# gpi-ctl.net
KiCad netlist of a schematic drawn in EAGLE
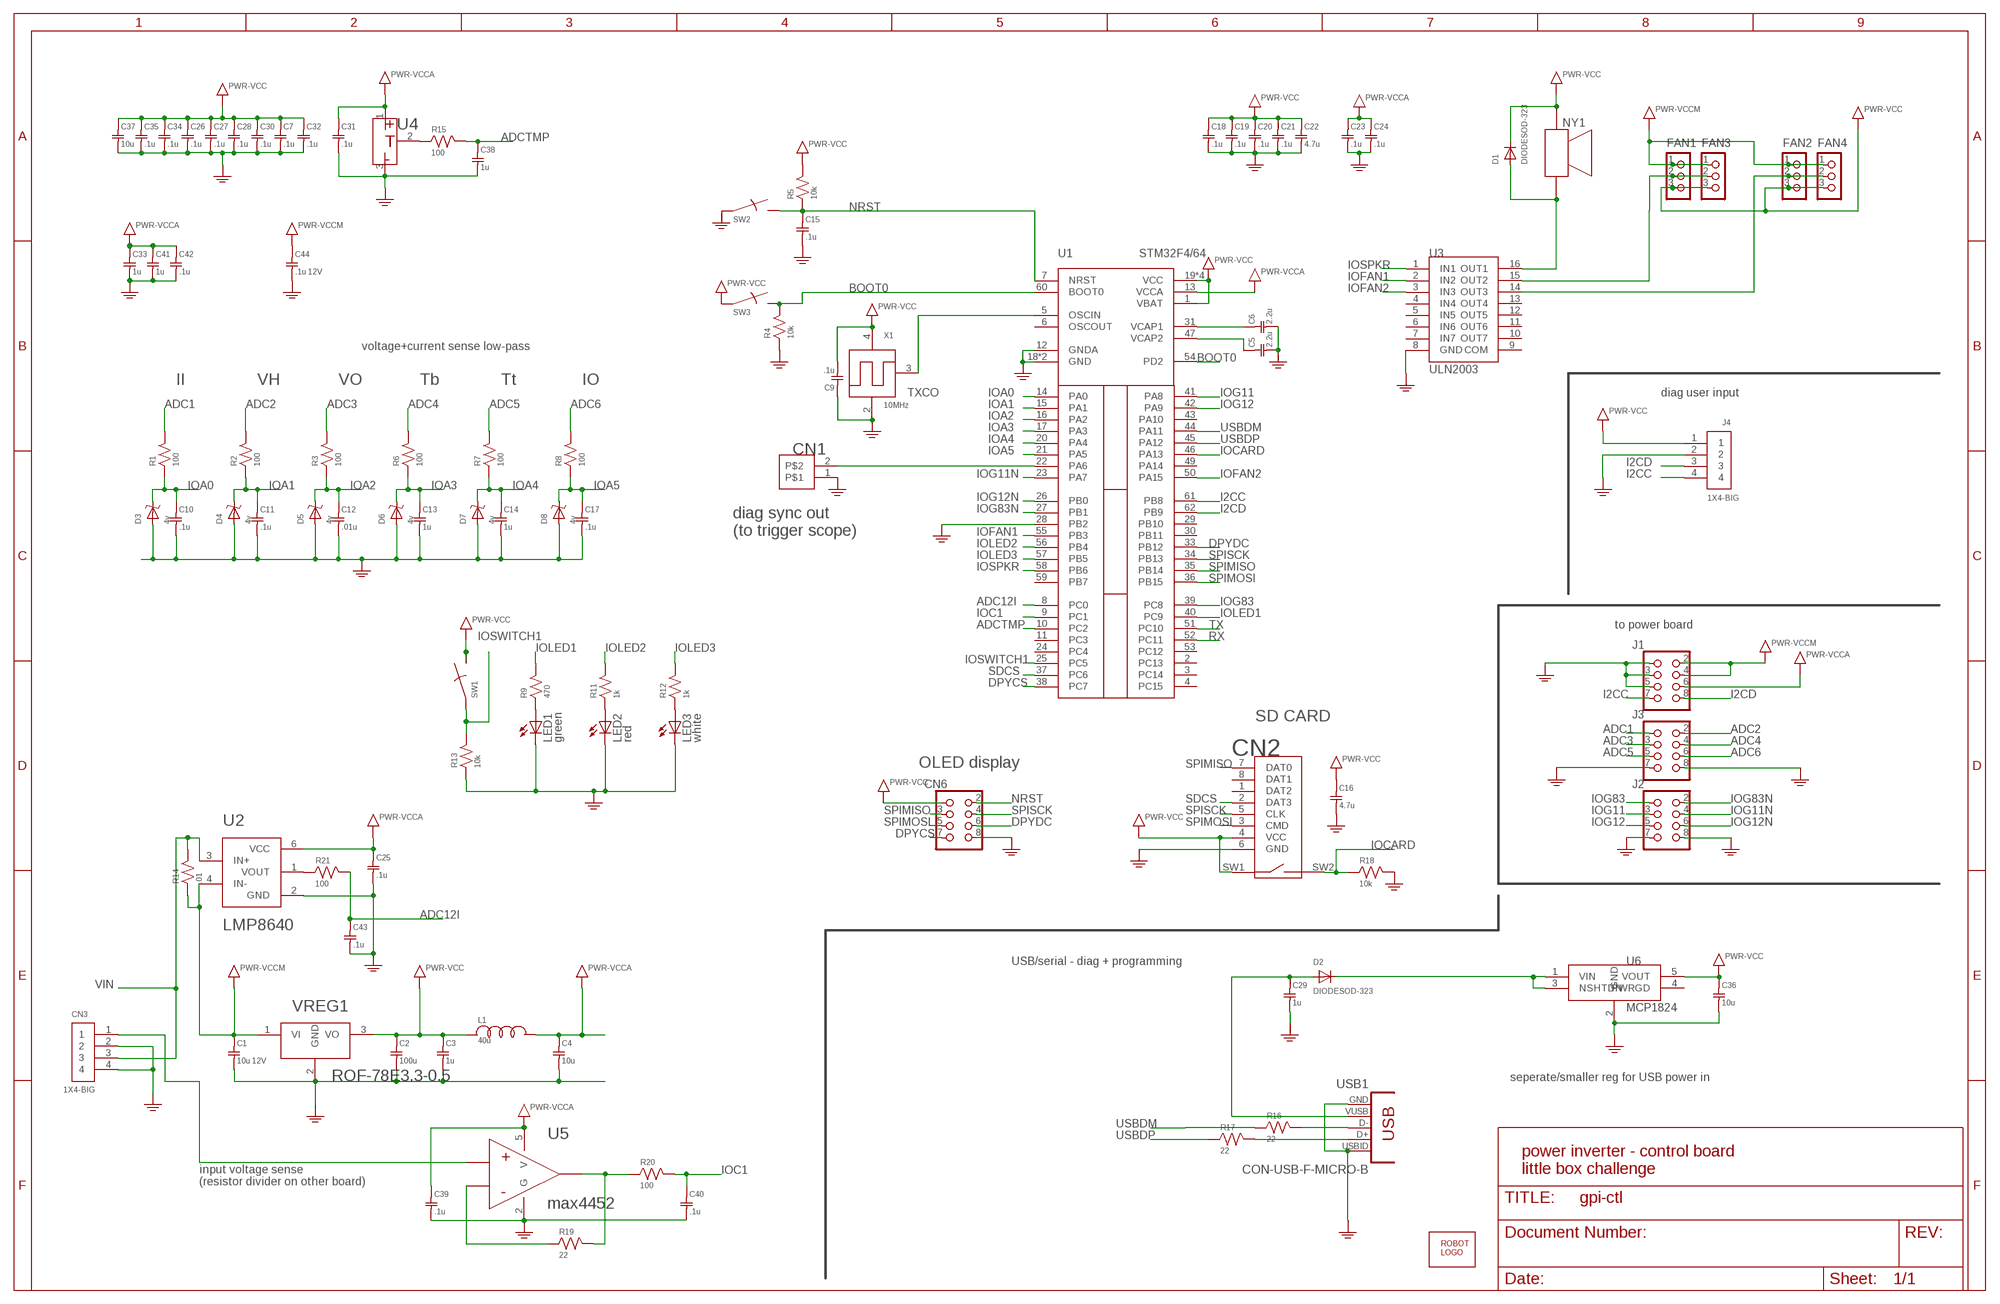
[diagram p0: schematic, sheet 1]

(export (version "E")
  (design (tool "Eeschema 10.0.6"))
  (components
    (comp (ref "C1")
      (value "10u 12V")
      (footprint "eagle-import:SMD0603")
      (libsource (lib "eagle-import") (part "C0603"))
    )
    (comp (ref "C2")
      (value "100u")
      (footprint "eagle-import:SMD1210")
      (libsource (lib "eagle-import") (part "C1210"))
    )
    (comp (ref "C3")
      (value "1u")
      (footprint "eagle-import:SMD0603")
      (libsource (lib "eagle-import") (part "C0603"))
    )
    (comp (ref "C4")
      (value "10u")
      (footprint "eagle-import:SMD0603")
      (libsource (lib "eagle-import") (part "C0603"))
    )
    (comp (ref "C5")
      (value "2.2u")
      (footprint "eagle-import:SMD0603")
      (libsource (lib "eagle-import") (part "C0603"))
    )
    (comp (ref "C6")
      (value "2.2u")
      (footprint "eagle-import:SMD0603")
      (libsource (lib "eagle-import") (part "C0603"))
    )
    (comp (ref "C7")
      (value ".1u")
      (footprint "eagle-import:SMD0603")
      (libsource (lib "eagle-import") (part "C0603"))
    )
    (comp (ref "C9")
      (value ".1u")
      (footprint "eagle-import:SMD0603")
      (libsource (lib "eagle-import") (part "C0603"))
    )
    (comp (ref "C10")
      (value ".1u")
      (footprint "eagle-import:SMD0603")
      (libsource (lib "eagle-import") (part "C0603"))
    )
    (comp (ref "C11")
      (value ".1u")
      (footprint "eagle-import:SMD0603")
      (libsource (lib "eagle-import") (part "C0603"))
    )
    (comp (ref "C12")
      (value ".01u")
      (footprint "eagle-import:SMD0603")
      (libsource (lib "eagle-import") (part "C0603"))
    )
    (comp (ref "C13")
      (value "1u")
      (footprint "eagle-import:SMD0603")
      (libsource (lib "eagle-import") (part "C0603"))
    )
    (comp (ref "C14")
      (value "1u")
      (footprint "eagle-import:SMD0603")
      (libsource (lib "eagle-import") (part "C0603"))
    )
    (comp (ref "C15")
      (value ".1u")
      (footprint "eagle-import:SMD0603")
      (libsource (lib "eagle-import") (part "C0603"))
    )
    (comp (ref "C16")
      (value "4.7u")
      (footprint "eagle-import:SMD0603")
      (libsource (lib "eagle-import") (part "C0603"))
    )
    (comp (ref "C17")
      (value ".1u")
      (footprint "eagle-import:SMD0603")
      (libsource (lib "eagle-import") (part "C0603"))
    )
    (comp (ref "C18")
      (value ".1u")
      (footprint "eagle-import:SMD0603")
      (libsource (lib "eagle-import") (part "C0603"))
    )
    (comp (ref "C19")
      (value ".1u")
      (footprint "eagle-import:SMD0603")
      (libsource (lib "eagle-import") (part "C0603"))
    )
    (comp (ref "C20")
      (value ".1u")
      (footprint "eagle-import:SMD0603")
      (libsource (lib "eagle-import") (part "C0603"))
    )
    (comp (ref "C21")
      (value ".1u")
      (footprint "eagle-import:SMD0603")
      (libsource (lib "eagle-import") (part "C0603"))
    )
    (comp (ref "C22")
      (value "4.7u")
      (footprint "eagle-import:SMD0603")
      (libsource (lib "eagle-import") (part "C0603"))
    )
    (comp (ref "C23")
      (value ".1u")
      (footprint "eagle-import:SMD0603")
      (libsource (lib "eagle-import") (part "C0603"))
    )
    (comp (ref "C24")
      (value ".1u")
      (footprint "eagle-import:SMD0603")
      (libsource (lib "eagle-import") (part "C0603"))
    )
    (comp (ref "C25")
      (value ".1u")
      (footprint "eagle-import:SMD0603")
      (libsource (lib "eagle-import") (part "C0603"))
    )
    (comp (ref "C26")
      (value ".1u")
      (footprint "eagle-import:SMD0603")
      (libsource (lib "eagle-import") (part "C0603"))
    )
    (comp (ref "C27")
      (value ".1u")
      (footprint "eagle-import:SMD0603")
      (libsource (lib "eagle-import") (part "C0603"))
    )
    (comp (ref "C28")
      (value ".1u")
      (footprint "eagle-import:SMD0603")
      (libsource (lib "eagle-import") (part "C0603"))
    )
    (comp (ref "C29")
      (value "1u")
      (footprint "eagle-import:SMD0603")
      (libsource (lib "eagle-import") (part "C0603"))
    )
    (comp (ref "C30")
      (value ".1u")
      (footprint "eagle-import:SMD0603")
      (libsource (lib "eagle-import") (part "C0603"))
    )
    (comp (ref "C31")
      (value ".1u")
      (footprint "eagle-import:SMD0603")
      (libsource (lib "eagle-import") (part "C0603"))
    )
    (comp (ref "C32")
      (value ".1u")
      (footprint "eagle-import:SMD0603")
      (libsource (lib "eagle-import") (part "C0603"))
    )
    (comp (ref "C33")
      (value "1u")
      (footprint "eagle-import:SMD0603")
      (libsource (lib "eagle-import") (part "C0603"))
    )
    (comp (ref "C34")
      (value ".1u")
      (footprint "eagle-import:SMD0603")
      (libsource (lib "eagle-import") (part "C0603"))
    )
    (comp (ref "C35")
      (value ".1u")
      (footprint "eagle-import:SMD0603")
      (libsource (lib "eagle-import") (part "C0603"))
    )
    (comp (ref "C36")
      (value "10u")
      (footprint "eagle-import:SMD0603")
      (libsource (lib "eagle-import") (part "C0603"))
    )
    (comp (ref "C37")
      (value "10u")
      (footprint "eagle-import:SMD0603")
      (libsource (lib "eagle-import") (part "C0603"))
    )
    (comp (ref "C38")
      (value "1u")
      (footprint "eagle-import:SMD0603")
      (libsource (lib "eagle-import") (part "C0603"))
    )
    (comp (ref "C39")
      (value ".1u")
      (footprint "eagle-import:SMD0603")
      (libsource (lib "eagle-import") (part "C0603"))
    )
    (comp (ref "C40")
      (value ".1u")
      (footprint "eagle-import:SMD0603")
      (libsource (lib "eagle-import") (part "C0603"))
    )
    (comp (ref "C41")
      (value "1u")
      (footprint "eagle-import:SMD0603")
      (libsource (lib "eagle-import") (part "C0603"))
    )
    (comp (ref "C42")
      (value ".1u")
      (footprint "eagle-import:SMD0603")
      (libsource (lib "eagle-import") (part "C0603"))
    )
    (comp (ref "C43")
      (value ".1u")
      (footprint "eagle-import:SMD0603")
      (libsource (lib "eagle-import") (part "C0603"))
    )
    (comp (ref "C44")
      (value ".1u 12V")
      (footprint "eagle-import:SMD0603")
      (libsource (lib "eagle-import") (part "C0603"))
    )
    (comp (ref "CN1")
      (value "HEADER-1X2.4")
      (footprint "eagle-import:HEADER-1X2-THM-WIDE")
      (libsource (lib "eagle-import") (part "HEADER-1X2.4"))
    )
    (comp (ref "CN2")
      (value "MICROSDPLAIN")
      (footprint "eagle-import:MICROSD_MOLEX_FRONT_PLAIN")
      (libsource (lib "eagle-import") (part "MICROSDPLAIN"))
    )
    (comp (ref "CN3")
      (value "1X4-BIG")
      (footprint "eagle-import:1X04-BIG")
      (libsource (lib "eagle-import") (part "1X4-BIG"))
    )
    (comp (ref "CN6")
      (value "HEADER-2X4")
      (footprint "eagle-import:HEADER-2X04")
      (libsource (lib "eagle-import") (part "HEADER-2X4"))
    )
    (comp (ref "D1")
      (value "DIODESOD-323")
      (footprint "eagle-import:SOD-323")
      (libsource (lib "eagle-import") (part "DIODESOD-323"))
    )
    (comp (ref "D2")
      (value "DIODESOD-323")
      (footprint "eagle-import:SOD-323")
      (libsource (lib "eagle-import") (part "DIODESOD-323"))
    )
    (comp (ref "D3")
      (value "4v")
      (footprint "eagle-import:SOD-323")
      (libsource (lib "eagle-import") (part "ZENER"))
    )
    (comp (ref "D4")
      (value "4v")
      (footprint "eagle-import:SOD-323")
      (libsource (lib "eagle-import") (part "ZENER"))
    )
    (comp (ref "D5")
      (value "4v")
      (footprint "eagle-import:SOD-323")
      (libsource (lib "eagle-import") (part "ZENER"))
    )
    (comp (ref "D6")
      (value "4v")
      (footprint "eagle-import:SOD-323")
      (libsource (lib "eagle-import") (part "ZENER"))
    )
    (comp (ref "D7")
      (value "4v")
      (footprint "eagle-import:SOD-323")
      (libsource (lib "eagle-import") (part "ZENER"))
    )
    (comp (ref "D8")
      (value "4v")
      (footprint "eagle-import:SOD-323")
      (libsource (lib "eagle-import") (part "ZENER"))
    )
    (comp (ref "FAN1")
      (value "CON_HEADER_1X03-PTH")
      (footprint "eagle-import:M1X3")
      (libsource (lib "eagle-import") (part "CON_HEADER_1X03-PTH"))
    )
    (comp (ref "FAN2")
      (value "CON_HEADER_1X03-PTH")
      (footprint "eagle-import:M1X3")
      (libsource (lib "eagle-import") (part "CON_HEADER_1X03-PTH"))
    )
    (comp (ref "FAN3")
      (value "CON_HEADER_1X03-PTH")
      (footprint "eagle-import:M1X3")
      (libsource (lib "eagle-import") (part "CON_HEADER_1X03-PTH"))
    )
    (comp (ref "FAN4")
      (value "CON_HEADER_1X03-PTH")
      (footprint "eagle-import:M1X3")
      (libsource (lib "eagle-import") (part "CON_HEADER_1X03-PTH"))
    )
    (comp (ref "J1")
      (value "HEADER-2X4")
      (footprint "eagle-import:HEADER-2X04")
      (libsource (lib "eagle-import") (part "HEADER-2X4"))
    )
    (comp (ref "J2")
      (value "HEADER-2X4")
      (footprint "eagle-import:HEADER-2X04")
      (libsource (lib "eagle-import") (part "HEADER-2X4"))
    )
    (comp (ref "J3")
      (value "HEADER-2X4")
      (footprint "eagle-import:HEADER-2X04")
      (libsource (lib "eagle-import") (part "HEADER-2X4"))
    )
    (comp (ref "J4")
      (value "1X4-BIG")
      (footprint "eagle-import:1X04-BIG")
      (libsource (lib "eagle-import") (part "1X4-BIG"))
    )
    (comp (ref "L1")
      (value "40u")
      (footprint "eagle-import:SMD0603")
      (libsource (lib "eagle-import") (part "LSMD0603"))
    )
    (comp (ref "LED1")
      (value "green")
      (footprint "eagle-import:LED3MM")
      (libsource (lib "eagle-import") (part "LED3MM"))
    )
    (comp (ref "LED2")
      (value "red")
      (footprint "eagle-import:LED3MM")
      (libsource (lib "eagle-import") (part "LED3MM"))
    )
    (comp (ref "LED3")
      (value "white")
      (footprint "eagle-import:LED3MM")
      (libsource (lib "eagle-import") (part "LED3MM"))
    )
    (comp (ref "NY1")
      (value "PUI-5040")
      (footprint "eagle-import:PUI-0540")
      (libsource (lib "eagle-import") (part "PUI-5040"))
    )
    (comp (ref "R1")
      (value "100")
      (footprint "eagle-import:SMD0603")
      (libsource (lib "eagle-import") (part "R0603"))
    )
    (comp (ref "R2")
      (value "100")
      (footprint "eagle-import:SMD0603")
      (libsource (lib "eagle-import") (part "R0603"))
    )
    (comp (ref "R3")
      (value "100")
      (footprint "eagle-import:SMD0603")
      (libsource (lib "eagle-import") (part "R0603"))
    )
    (comp (ref "R4")
      (value "10k")
      (footprint "eagle-import:SMD0603")
      (libsource (lib "eagle-import") (part "R0603"))
    )
    (comp (ref "R5")
      (value "10k")
      (footprint "eagle-import:SMD0603")
      (libsource (lib "eagle-import") (part "R0603"))
    )
    (comp (ref "R6")
      (value "100")
      (footprint "eagle-import:SMD0603")
      (libsource (lib "eagle-import") (part "R0603"))
    )
    (comp (ref "R7")
      (value "100")
      (footprint "eagle-import:SMD0603")
      (libsource (lib "eagle-import") (part "R0603"))
    )
    (comp (ref "R8")
      (value "100")
      (footprint "eagle-import:SMD0603")
      (libsource (lib "eagle-import") (part "R0603"))
    )
    (comp (ref "R9")
      (value "470")
      (footprint "eagle-import:SMD0603")
      (libsource (lib "eagle-import") (part "R0603"))
    )
    (comp (ref "R11")
      (value "1k")
      (footprint "eagle-import:SMD0603")
      (libsource (lib "eagle-import") (part "R0603"))
    )
    (comp (ref "R12")
      (value "1k")
      (footprint "eagle-import:SMD0603")
      (libsource (lib "eagle-import") (part "R0603"))
    )
    (comp (ref "R13")
      (value "10k")
      (footprint "eagle-import:SMD0603")
      (libsource (lib "eagle-import") (part "R0603"))
    )
    (comp (ref "R14")
      (value ".01")
      (footprint "eagle-import:SMD0805")
      (libsource (lib "eagle-import") (part "R0805"))
    )
    (comp (ref "R15")
      (value "100")
      (footprint "eagle-import:SMD0603")
      (libsource (lib "eagle-import") (part "R0603"))
    )
    (comp (ref "R16")
      (value "22")
      (footprint "eagle-import:SMD0603")
      (libsource (lib "eagle-import") (part "R0603"))
    )
    (comp (ref "R17")
      (value "22")
      (footprint "eagle-import:SMD0603")
      (libsource (lib "eagle-import") (part "R0603"))
    )
    (comp (ref "R18")
      (value "10k")
      (footprint "eagle-import:SMD0603")
      (libsource (lib "eagle-import") (part "R0603"))
    )
    (comp (ref "R19")
      (value "22")
      (footprint "eagle-import:SMD0603")
      (libsource (lib "eagle-import") (part "R0603"))
    )
    (comp (ref "R20")
      (value "100")
      (footprint "eagle-import:SMD0603")
      (libsource (lib "eagle-import") (part "R0603"))
    )
    (comp (ref "R21")
      (value "100")
      (footprint "eagle-import:SMD0603")
      (libsource (lib "eagle-import") (part "R0603"))
    )
    (comp (ref "SW1")
      (value "SWITCHGT12-THOLE")
      (footprint "eagle-import:SWITCH-GT12MCBE")
      (libsource (lib "eagle-import") (part "SWITCHGT12-THOLE"))
    )
    (comp (ref "SW2")
      (value "SWITCHKMR211")
      (footprint "eagle-import:KMR211")
      (libsource (lib "eagle-import") (part "SWITCHKMR211"))
    )
    (comp (ref "SW3")
      (value "SWITCHKMR211")
      (footprint "eagle-import:KMR211")
      (libsource (lib "eagle-import") (part "SWITCHKMR211"))
    )
    (comp (ref "U$1")
      (value "ROBOTMAN-LOGO")
      (footprint "eagle-import:ROBOTMAN-LOGO")
      (libsource (lib "eagle-import") (part "ROBOTMAN-LOGO"))
    )
    (comp (ref "U1")
      (value "STM32F4/64")
      (footprint "eagle-import:TQFP64")
      (libsource (lib "eagle-import") (part "STM32F4/64"))
    )
    (comp (ref "U2")
      (value "LMP8640")
      (footprint "eagle-import:SOT-6")
      (libsource (lib "eagle-import") (part "LMP8640"))
    )
    (comp (ref "U3")
      (value "ULN2003")
      (footprint "eagle-import:TSSOP-16")
      (libsource (lib "eagle-import") (part "ULN2003"))
    )
    (comp (ref "U4")
      (value "TEMPERATURE")
      (footprint "eagle-import:SOT-23")
      (libsource (lib "eagle-import") (part "TEMPERATURE"))
    )
    (comp (ref "U5")
      (value "max4452")
      (footprint "eagle-import:SOT-23-5")
      (libsource (lib "eagle-import") (part "OPAMP"))
    )
    (comp (ref "U6")
      (value "MCP1824")
      (footprint "eagle-import:SOT-23-5")
      (libsource (lib "eagle-import") (part "MCP1824"))
    )
    (comp (ref "USB1")
      (value "CON-USB-F-MICRO-B")
      (footprint "eagle-import:CONN_USB_MICRO-B")
      (libsource (lib "eagle-import") (part "CON-USB-F-MICRO-B"))
    )
    (comp (ref "VREG1")
      (value "ROF-78E3.3-0.5")
      (footprint "eagle-import:ROF7800")
      (libsource (lib "eagle-import") (part "REGULATORROF"))
    )
    (comp (ref "X1")
      (value "10MHz")
      (footprint "eagle-import:OSC-AST3TQ")
      (libsource (lib "eagle-import") (part "OSC"))
    )
  )
  (nets
    (net (code "1") (name "/ADC1") (class "Default")
      (node (ref "J3") (pin "1") (pinfunction "P$1_1") (pintype "passive"))
      (node (ref "R1") (pin "2") (pinfunction "P$2_2") (pintype "passive"))
    )
    (net (code "2") (name "/ADC2") (class "Default")
      (node (ref "J3") (pin "2") (pinfunction "P$2_2") (pintype "passive"))
      (node (ref "R2") (pin "2") (pinfunction "P$2_2") (pintype "passive"))
    )
    (net (code "3") (name "/ADC3") (class "Default")
      (node (ref "J3") (pin "3") (pinfunction "P$3_3") (pintype "passive"))
      (node (ref "R3") (pin "2") (pinfunction "P$2_2") (pintype "passive"))
    )
    (net (code "4") (name "/ADC4") (class "Default")
      (node (ref "J3") (pin "4") (pinfunction "P$4_4") (pintype "passive"))
      (node (ref "R6") (pin "2") (pinfunction "P$2_2") (pintype "passive"))
    )
    (net (code "5") (name "/ADC5") (class "Default")
      (node (ref "J3") (pin "5") (pinfunction "P$5_5") (pintype "passive"))
      (node (ref "R7") (pin "2") (pinfunction "P$2_2") (pintype "passive"))
    )
    (net (code "6") (name "/ADC6") (class "Default")
      (node (ref "J3") (pin "6") (pinfunction "P$6_6") (pintype "passive"))
      (node (ref "R8") (pin "2") (pinfunction "P$2_2") (pintype "passive"))
    )
    (net (code "7") (name "/ADC12I") (class "Default")
      (node (ref "C43") (pin "1") (pinfunction "P$1_1") (pintype "passive"))
      (node (ref "R21") (pin "2") (pinfunction "P$2_2") (pintype "passive"))
      (node (ref "U1") (pin "8") (pinfunction "PC0_8") (pintype "bidirectional"))
    )
    (net (code "8") (name "/ADCTMP") (class "Default")
      (node (ref "C38") (pin "1") (pinfunction "P$1_1") (pintype "passive"))
      (node (ref "R15") (pin "2") (pinfunction "P$2_2") (pintype "passive"))
      (node (ref "U1") (pin "10") (pinfunction "PC2_10") (pintype "bidirectional"))
    )
    (net (code "9") (name "/BOOT0") (class "Default")
      (node (ref "R4") (pin "2") (pinfunction "P$2_2") (pintype "passive"))
      (node (ref "SW3") (pin "2") (pinfunction "P$2_2") (pintype "passive"))
      (node (ref "SW3") (pin "4") (pinfunction "P$2_4") (pintype "passive"))
      (node (ref "U1") (pin "54") (pinfunction "PD2_54") (pintype "bidirectional"))
      (node (ref "U1") (pin "60") (pinfunction "BOOT0_60") (pintype "bidirectional"))
    )
    (net (code "10") (name "/DPYCS") (class "Default")
      (node (ref "CN6") (pin "7") (pinfunction "P$7_7") (pintype "passive"))
      (node (ref "U1") (pin "38") (pinfunction "PC7_38") (pintype "bidirectional"))
    )
    (net (code "11") (name "/DPYDC") (class "Default")
      (node (ref "CN6") (pin "6") (pinfunction "P$6_6") (pintype "passive"))
      (node (ref "U1") (pin "33") (pinfunction "PB12_33") (pintype "bidirectional"))
    )
    (net (code "12") (name "/I2CC") (class "Default")
      (node (ref "J1") (pin "7") (pinfunction "P$7_7") (pintype "passive"))
      (node (ref "J4") (pin "4") (pinfunction "4_4") (pintype "bidirectional"))
      (node (ref "U1") (pin "61") (pinfunction "PB8_61") (pintype "bidirectional"))
    )
    (net (code "13") (name "/I2CD") (class "Default")
      (node (ref "J1") (pin "8") (pinfunction "P$8_8") (pintype "passive"))
      (node (ref "J4") (pin "3") (pinfunction "3_3") (pintype "bidirectional"))
      (node (ref "U1") (pin "62") (pinfunction "PB9_62") (pintype "bidirectional"))
    )
    (net (code "14") (name "/IOA0") (class "Default")
      (node (ref "C10") (pin "1") (pinfunction "P$1_1") (pintype "passive"))
      (node (ref "D3") (pin "C") (pinfunction "C_C") (pintype "passive"))
      (node (ref "R1") (pin "1") (pinfunction "P$1_1") (pintype "passive"))
      (node (ref "U1") (pin "14") (pinfunction "PA0_14") (pintype "bidirectional"))
    )
    (net (code "15") (name "/IOA1") (class "Default")
      (node (ref "C11") (pin "1") (pinfunction "P$1_1") (pintype "passive"))
      (node (ref "D4") (pin "C") (pinfunction "C_C") (pintype "passive"))
      (node (ref "R2") (pin "1") (pinfunction "P$1_1") (pintype "passive"))
      (node (ref "U1") (pin "15") (pinfunction "PA1_15") (pintype "bidirectional"))
    )
    (net (code "16") (name "/IOA2") (class "Default")
      (node (ref "C12") (pin "1") (pinfunction "P$1_1") (pintype "passive"))
      (node (ref "D5") (pin "C") (pinfunction "C_C") (pintype "passive"))
      (node (ref "R3") (pin "1") (pinfunction "P$1_1") (pintype "passive"))
      (node (ref "U1") (pin "16") (pinfunction "PA2_16") (pintype "bidirectional"))
    )
    (net (code "17") (name "/IOA3") (class "Default")
      (node (ref "C13") (pin "1") (pinfunction "P$1_1") (pintype "passive"))
      (node (ref "D6") (pin "C") (pinfunction "C_C") (pintype "passive"))
      (node (ref "R6") (pin "1") (pinfunction "P$1_1") (pintype "passive"))
      (node (ref "U1") (pin "17") (pinfunction "PA3_17") (pintype "bidirectional"))
    )
    (net (code "18") (name "/IOA4") (class "Default")
      (node (ref "C14") (pin "1") (pinfunction "P$1_1") (pintype "passive"))
      (node (ref "D7") (pin "C") (pinfunction "C_C") (pintype "passive"))
      (node (ref "R7") (pin "1") (pinfunction "P$1_1") (pintype "passive"))
      (node (ref "U1") (pin "20") (pinfunction "PA4_20") (pintype "bidirectional"))
    )
    (net (code "19") (name "/IOA5") (class "Default")
      (node (ref "C17") (pin "1") (pinfunction "P$1_1") (pintype "passive"))
      (node (ref "D8") (pin "C") (pinfunction "C_C") (pintype "passive"))
      (node (ref "R8") (pin "1") (pinfunction "P$1_1") (pintype "passive"))
      (node (ref "U1") (pin "21") (pinfunction "PA5_21") (pintype "bidirectional"))
    )
    (net (code "20") (name "/IOC1") (class "Default")
      (node (ref "C40") (pin "1") (pinfunction "P$1_1") (pintype "passive"))
      (node (ref "R20") (pin "2") (pinfunction "P$2_2") (pintype "passive"))
      (node (ref "U1") (pin "9") (pinfunction "PC1_9") (pintype "bidirectional"))
    )
    (net (code "21") (name "/IOCARD") (class "Default")
      (node (ref "CN2") (pin "SW2") (pinfunction "SW2_SW2") (pintype "bidirectional"))
      (node (ref "R18") (pin "1") (pinfunction "P$1_1") (pintype "passive"))
      (node (ref "U1") (pin "46") (pinfunction "PA13_46") (pintype "bidirectional"))
    )
    (net (code "22") (name "/IOFAN1") (class "Default")
      (node (ref "U1") (pin "55") (pinfunction "PB3_55") (pintype "bidirectional"))
      (node (ref "U3") (pin "2") (pinfunction "IN2_2") (pintype "input"))
    )
    (net (code "23") (name "/IOFAN2") (class "Default")
      (node (ref "U1") (pin "50") (pinfunction "PA15_50") (pintype "bidirectional"))
      (node (ref "U3") (pin "3") (pinfunction "IN3_3") (pintype "input"))
    )
    (net (code "24") (name "/IOG11") (class "Default")
      (node (ref "J2") (pin "3") (pinfunction "P$3_3") (pintype "passive"))
      (node (ref "U1") (pin "41") (pinfunction "PA8_41") (pintype "bidirectional"))
    )
    (net (code "25") (name "/IOG11N") (class "Default")
      (node (ref "J2") (pin "4") (pinfunction "P$4_4") (pintype "passive"))
      (node (ref "U1") (pin "23") (pinfunction "PA7_23") (pintype "bidirectional"))
    )
    (net (code "26") (name "/IOG12") (class "Default")
      (node (ref "J2") (pin "5") (pinfunction "P$5_5") (pintype "passive"))
      (node (ref "U1") (pin "42") (pinfunction "PA9_42") (pintype "bidirectional"))
    )
    (net (code "27") (name "/IOG12N") (class "Default")
      (node (ref "J2") (pin "6") (pinfunction "P$6_6") (pintype "passive"))
      (node (ref "U1") (pin "26") (pinfunction "PB0_26") (pintype "bidirectional"))
    )
    (net (code "28") (name "/IOG83") (class "Default")
      (node (ref "J2") (pin "1") (pinfunction "P$1_1") (pintype "passive"))
      (node (ref "U1") (pin "39") (pinfunction "PC8_39") (pintype "bidirectional"))
    )
    (net (code "29") (name "/IOG83N") (class "Default")
      (node (ref "J2") (pin "2") (pinfunction "P$2_2") (pintype "passive"))
      (node (ref "U1") (pin "27") (pinfunction "PB1_27") (pintype "bidirectional"))
    )
    (net (code "30") (name "/IOLED1") (class "Default")
      (node (ref "R9") (pin "2") (pinfunction "P$2_2") (pintype "passive"))
      (node (ref "U1") (pin "40") (pinfunction "PC9_40") (pintype "bidirectional"))
    )
    (net (code "31") (name "/IOLED2") (class "Default")
      (node (ref "R11") (pin "2") (pinfunction "P$2_2") (pintype "passive"))
      (node (ref "U1") (pin "56") (pinfunction "PB4_56") (pintype "bidirectional"))
    )
    (net (code "32") (name "/IOLED3") (class "Default")
      (node (ref "R12") (pin "2") (pinfunction "P$2_2") (pintype "passive"))
      (node (ref "U1") (pin "57") (pinfunction "PB5_57") (pintype "bidirectional"))
    )
    (net (code "33") (name "/IOSPKR") (class "Default")
      (node (ref "U1") (pin "58") (pinfunction "PB6_58") (pintype "bidirectional"))
      (node (ref "U3") (pin "1") (pinfunction "IN1_1") (pintype "input"))
    )
    (net (code "34") (name "/IOSWITCH1") (class "Default")
      (node (ref "R13") (pin "2") (pinfunction "P$2_2") (pintype "passive"))
      (node (ref "SW1") (pin "1") (pinfunction "P$1_1") (pintype "passive"))
      (node (ref "U1") (pin "25") (pinfunction "PC5_25") (pintype "bidirectional"))
    )
    (net (code "35") (name "/NRST") (class "Default")
      (node (ref "C15") (pin "1") (pinfunction "P$1_1") (pintype "passive"))
      (node (ref "CN6") (pin "2") (pinfunction "P$2_2") (pintype "passive"))
      (node (ref "R5") (pin "1") (pinfunction "P$1_1") (pintype "passive"))
      (node (ref "SW2") (pin "2") (pinfunction "P$2_2") (pintype "passive"))
      (node (ref "SW2") (pin "4") (pinfunction "P$2_4") (pintype "passive"))
      (node (ref "U1") (pin "7") (pinfunction "NRST_7") (pintype "bidirectional"))
    )
    (net (code "36") (name "/RX") (class "Default")
      (node (ref "U1") (pin "52") (pinfunction "PC11_52") (pintype "bidirectional"))
    )
    (net (code "37") (name "/SDCS") (class "Default")
      (node (ref "CN2") (pin "2") (pinfunction "DAT3_2") (pintype "bidirectional"))
      (node (ref "U1") (pin "37") (pinfunction "PC6_37") (pintype "bidirectional"))
    )
    (net (code "38") (name "/SPIMISO") (class "Default")
      (node (ref "CN2") (pin "7") (pinfunction "DAT0_7") (pintype "bidirectional"))
      (node (ref "CN6") (pin "3") (pinfunction "P$3_3") (pintype "passive"))
      (node (ref "U1") (pin "35") (pinfunction "PB14_35") (pintype "bidirectional"))
    )
    (net (code "39") (name "/SPIMOSI") (class "Default")
      (node (ref "CN2") (pin "3") (pinfunction "CMD_3") (pintype "bidirectional"))
      (node (ref "CN6") (pin "5") (pinfunction "P$5_5") (pintype "passive"))
      (node (ref "U1") (pin "36") (pinfunction "PB15_36") (pintype "bidirectional"))
    )
    (net (code "40") (name "/SPISCK") (class "Default")
      (node (ref "CN2") (pin "5") (pinfunction "CLK_5") (pintype "bidirectional"))
      (node (ref "CN6") (pin "4") (pinfunction "P$4_4") (pintype "passive"))
      (node (ref "U1") (pin "34") (pinfunction "PB13_34") (pintype "bidirectional"))
    )
    (net (code "41") (name "/TX") (class "Default")
      (node (ref "U1") (pin "51") (pinfunction "PC10_51") (pintype "bidirectional"))
    )
    (net (code "42") (name "/USBDM") (class "Default")
      (node (ref "R16") (pin "1") (pinfunction "P$1_1") (pintype "passive"))
      (node (ref "U1") (pin "44") (pinfunction "PA11_44") (pintype "bidirectional"))
    )
    (net (code "43") (name "/USBDP") (class "Default")
      (node (ref "R17") (pin "1") (pinfunction "P$1_1") (pintype "passive"))
      (node (ref "U1") (pin "45") (pinfunction "PA12_45") (pintype "bidirectional"))
    )
    (net (code "44") (name "/VIN") (class "Default")
      (node (ref "CN3") (pin "3") (pinfunction "3_3") (pintype "bidirectional"))
      (node (ref "R14") (pin "2") (pinfunction "P$2_2") (pintype "passive"))
      (node (ref "U2") (pin "3") (pinfunction "IN+_3") (pintype "bidirectional"))
    )
    (net (code "45") (name "Net-(C5-P$1)") (class "Default")
      (node (ref "C5") (pin "1") (pinfunction "P$1_1") (pintype "passive"))
      (node (ref "U1") (pin "47") (pinfunction "VCAP2_47") (pintype "bidirectional"))
    )
    (net (code "46") (name "Net-(C6-P$1)") (class "Default")
      (node (ref "C6") (pin "1") (pinfunction "P$1_1") (pintype "passive"))
      (node (ref "U1") (pin "31") (pinfunction "VCAP1_31") (pintype "bidirectional"))
    )
    (net (code "47") (name "Net-(C29-P$1)") (class "Default")
      (node (ref "C29") (pin "1") (pinfunction "P$1_1") (pintype "passive"))
      (node (ref "D2") (pin "A") (pinfunction "A_A") (pintype "passive"))
      (node (ref "USB1") (pin "P1") (pinfunction "VUSB_P1") (pintype "bidirectional"))
    )
    (net (code "48") (name "Net-(CN1-P$2)") (class "Default")
      (node (ref "CN1") (pin "2") (pinfunction "P$2_2") (pintype "bidirectional"))
      (node (ref "U1") (pin "22") (pinfunction "PA6_22") (pintype "bidirectional"))
    )
    (net (code "49") (name "Net-(R9-P$1)") (class "Default")
      (node (ref "LED1") (pin "A") (pinfunction "A_A") (pintype "passive"))
      (node (ref "R9") (pin "1") (pinfunction "P$1_1") (pintype "passive"))
    )
    (net (code "50") (name "Net-(R11-P$1)") (class "Default")
      (node (ref "LED2") (pin "A") (pinfunction "A_A") (pintype "passive"))
      (node (ref "R11") (pin "1") (pinfunction "P$1_1") (pintype "passive"))
    )
    (net (code "51") (name "Net-(R12-P$1)") (class "Default")
      (node (ref "LED3") (pin "A") (pinfunction "A_A") (pintype "passive"))
      (node (ref "R12") (pin "1") (pinfunction "P$1_1") (pintype "passive"))
    )
    (net (code "52") (name "Net-(R15-P$1)") (class "Default")
      (node (ref "R15") (pin "1") (pinfunction "P$1_1") (pintype "passive"))
      (node (ref "U4") (pin "2") (pinfunction "OUT_2") (pintype "bidirectional"))
    )
    (net (code "53") (name "Net-(R16-P$2)") (class "Default")
      (node (ref "R16") (pin "2") (pinfunction "P$2_2") (pintype "passive"))
      (node (ref "USB1") (pin "P2") (pinfunction "D-_P2") (pintype "bidirectional"))
    )
    (net (code "54") (name "Net-(R17-P$2)") (class "Default")
      (node (ref "R17") (pin "2") (pinfunction "P$2_2") (pintype "passive"))
      (node (ref "USB1") (pin "P3") (pinfunction "D+_P3") (pintype "bidirectional"))
    )
    (net (code "55") (name "Net-(R19-P$1)") (class "Default")
      (node (ref "R19") (pin "1") (pinfunction "P$1_1") (pintype "passive"))
      (node (ref "U5") (pin "4") (pinfunction "INM_4") (pintype "bidirectional"))
    )
    (net (code "56") (name "Net-(R19-P$2)") (class "Default")
      (node (ref "R19") (pin "2") (pinfunction "P$2_2") (pintype "passive"))
      (node (ref "R20") (pin "1") (pinfunction "P$1_1") (pintype "passive"))
      (node (ref "U5") (pin "1") (pinfunction "OUT_1") (pintype "bidirectional"))
    )
    (net (code "57") (name "Net-(R21-P$1)") (class "Default")
      (node (ref "R21") (pin "1") (pinfunction "P$1_1") (pintype "passive"))
      (node (ref "U2") (pin "1") (pinfunction "VOUT_1") (pintype "bidirectional"))
    )
    (net (code "58") (name "Net-(U1-OSCIN)") (class "Default")
      (node (ref "U1") (pin "5") (pinfunction "OSCIN_5") (pintype "bidirectional"))
      (node (ref "X1") (pin "3") (pinfunction "OSC_3") (pintype "bidirectional"))
    )
    (net (code "59") (name "Net-(U3-OUT1)") (class "Default")
      (node (ref "D1") (pin "A") (pinfunction "A_A") (pintype "passive"))
      (node (ref "NY1") (pin "P2") (pinfunction "P2_P2") (pintype "input"))
      (node (ref "U3") (pin "16") (pinfunction "OUT1_16") (pintype "output"))
    )
    (net (code "60") (name "Net-(U3-OUT2)") (class "Default")
      (node (ref "FAN1") (pin "2") (pinfunction "2_2") (pintype "bidirectional"))
      (node (ref "FAN3") (pin "2") (pinfunction "2_2") (pintype "bidirectional"))
      (node (ref "U3") (pin "15") (pinfunction "OUT2_15") (pintype "output"))
    )
    (net (code "61") (name "Net-(U3-OUT3)") (class "Default")
      (node (ref "FAN2") (pin "2") (pinfunction "2_2") (pintype "bidirectional"))
      (node (ref "FAN4") (pin "2") (pinfunction "2_2") (pintype "bidirectional"))
      (node (ref "U3") (pin "14") (pinfunction "OUT3_14") (pintype "output"))
    )
    (net (code "62") (name "Net-(U5-INP)") (class "Default")
      (node (ref "CN3") (pin "1") (pinfunction "1_1") (pintype "bidirectional"))
      (node (ref "U5") (pin "3") (pinfunction "INP_3") (pintype "bidirectional"))
    )
    (net (code "63") (name "Net-(U6-NSHTDN)") (class "Default")
      (node (ref "D2") (pin "C") (pinfunction "C_C") (pintype "passive"))
      (node (ref "U6") (pin "1") (pinfunction "VIN_1") (pintype "bidirectional"))
      (node (ref "U6") (pin "3") (pinfunction "NSHTDN_3") (pintype "bidirectional"))
    )
    (net (code "64") (name "PWR-GND") (class "Default")
      (node (ref "C1") (pin "2") (pinfunction "P$2_2") (pintype "passive"))
      (node (ref "C10") (pin "2") (pinfunction "P$2_2") (pintype "passive"))
      (node (ref "C11") (pin "2") (pinfunction "P$2_2") (pintype "passive"))
      (node (ref "C12") (pin "2") (pinfunction "P$2_2") (pintype "passive"))
      (node (ref "C13") (pin "2") (pinfunction "P$2_2") (pintype "passive"))
      (node (ref "C14") (pin "2") (pinfunction "P$2_2") (pintype "passive"))
      (node (ref "C15") (pin "2") (pinfunction "P$2_2") (pintype "passive"))
      (node (ref "C16") (pin "2") (pinfunction "P$2_2") (pintype "passive"))
      (node (ref "C17") (pin "2") (pinfunction "P$2_2") (pintype "passive"))
      (node (ref "C18") (pin "2") (pinfunction "P$2_2") (pintype "passive"))
      (node (ref "C19") (pin "2") (pinfunction "P$2_2") (pintype "passive"))
      (node (ref "C2") (pin "2") (pinfunction "P$2_2") (pintype "passive"))
      (node (ref "C20") (pin "2") (pinfunction "P$2_2") (pintype "passive"))
      (node (ref "C21") (pin "2") (pinfunction "P$2_2") (pintype "passive"))
      (node (ref "C22") (pin "2") (pinfunction "P$2_2") (pintype "passive"))
      (node (ref "C23") (pin "2") (pinfunction "P$2_2") (pintype "passive"))
      (node (ref "C24") (pin "2") (pinfunction "P$2_2") (pintype "passive"))
      (node (ref "C25") (pin "2") (pinfunction "P$2_2") (pintype "passive"))
      (node (ref "C26") (pin "2") (pinfunction "P$2_2") (pintype "passive"))
      (node (ref "C27") (pin "2") (pinfunction "P$2_2") (pintype "passive"))
      (node (ref "C28") (pin "2") (pinfunction "P$2_2") (pintype "passive"))
      (node (ref "C29") (pin "2") (pinfunction "P$2_2") (pintype "passive"))
      (node (ref "C3") (pin "2") (pinfunction "P$2_2") (pintype "passive"))
      (node (ref "C30") (pin "2") (pinfunction "P$2_2") (pintype "passive"))
      (node (ref "C31") (pin "2") (pinfunction "P$2_2") (pintype "passive"))
      (node (ref "C32") (pin "2") (pinfunction "P$2_2") (pintype "passive"))
      (node (ref "C33") (pin "2") (pinfunction "P$2_2") (pintype "passive"))
      (node (ref "C34") (pin "2") (pinfunction "P$2_2") (pintype "passive"))
      (node (ref "C35") (pin "2") (pinfunction "P$2_2") (pintype "passive"))
      (node (ref "C36") (pin "2") (pinfunction "P$2_2") (pintype "passive"))
      (node (ref "C37") (pin "2") (pinfunction "P$2_2") (pintype "passive"))
      (node (ref "C38") (pin "2") (pinfunction "P$2_2") (pintype "passive"))
      (node (ref "C39") (pin "2") (pinfunction "P$2_2") (pintype "passive"))
      (node (ref "C4") (pin "2") (pinfunction "P$2_2") (pintype "passive"))
      (node (ref "C40") (pin "2") (pinfunction "P$2_2") (pintype "passive"))
      (node (ref "C41") (pin "2") (pinfunction "P$2_2") (pintype "passive"))
      (node (ref "C42") (pin "2") (pinfunction "P$2_2") (pintype "passive"))
      (node (ref "C43") (pin "2") (pinfunction "P$2_2") (pintype "passive"))
      (node (ref "C44") (pin "2") (pinfunction "P$2_2") (pintype "passive"))
      (node (ref "C5") (pin "2") (pinfunction "P$2_2") (pintype "passive"))
      (node (ref "C6") (pin "2") (pinfunction "P$2_2") (pintype "passive"))
      (node (ref "C7") (pin "2") (pinfunction "P$2_2") (pintype "passive"))
      (node (ref "C9") (pin "1") (pinfunction "P$1_1") (pintype "passive"))
      (node (ref "CN1") (pin "1") (pinfunction "P$1_1") (pintype "bidirectional"))
      (node (ref "CN2") (pin "6") (pinfunction "GND_6") (pintype "bidirectional"))
      (node (ref "CN3") (pin "2") (pinfunction "2_2") (pintype "bidirectional"))
      (node (ref "CN3") (pin "4") (pinfunction "4_4") (pintype "bidirectional"))
      (node (ref "CN6") (pin "8") (pinfunction "P$8_8") (pintype "passive"))
      (node (ref "D3") (pin "A") (pinfunction "A_A") (pintype "passive"))
      (node (ref "D4") (pin "A") (pinfunction "A_A") (pintype "passive"))
      (node (ref "D5") (pin "A") (pinfunction "A_A") (pintype "passive"))
      (node (ref "D6") (pin "A") (pinfunction "A_A") (pintype "passive"))
      (node (ref "D7") (pin "A") (pinfunction "A_A") (pintype "passive"))
      (node (ref "D8") (pin "A") (pinfunction "A_A") (pintype "passive"))
      (node (ref "J1") (pin "1") (pinfunction "P$1_1") (pintype "passive"))
      (node (ref "J1") (pin "3") (pinfunction "P$3_3") (pintype "passive"))
      (node (ref "J1") (pin "5") (pinfunction "P$5_5") (pintype "passive"))
      (node (ref "J2") (pin "7") (pinfunction "P$7_7") (pintype "passive"))
      (node (ref "J2") (pin "8") (pinfunction "P$8_8") (pintype "passive"))
      (node (ref "J3") (pin "7") (pinfunction "P$7_7") (pintype "passive"))
      (node (ref "J3") (pin "8") (pinfunction "P$8_8") (pintype "passive"))
      (node (ref "J4") (pin "2") (pinfunction "2_2") (pintype "bidirectional"))
      (node (ref "LED1") (pin "K") (pinfunction "C_K") (pintype "passive"))
      (node (ref "LED2") (pin "K") (pinfunction "C_K") (pintype "passive"))
      (node (ref "LED3") (pin "K") (pinfunction "C_K") (pintype "passive"))
      (node (ref "R13") (pin "1") (pinfunction "P$1_1") (pintype "passive"))
      (node (ref "R18") (pin "2") (pinfunction "P$2_2") (pintype "passive"))
      (node (ref "R4") (pin "1") (pinfunction "P$1_1") (pintype "passive"))
      (node (ref "SW2") (pin "1") (pinfunction "P$1_1") (pintype "passive"))
      (node (ref "SW2") (pin "3") (pinfunction "P$1_3") (pintype "passive"))
      (node (ref "U1") (pin "12") (pinfunction "GNDA_12") (pintype "bidirectional"))
      (node (ref "U1") (pin "18") (pinfunction "GND_18") (pintype "bidirectional"))
      (node (ref "U1") (pin "28") (pinfunction "PB2_28") (pintype "bidirectional"))
      (node (ref "U1") (pin "63") (pinfunction "GND_63") (pintype "bidirectional"))
      (node (ref "U2") (pin "2") (pinfunction "GND_2") (pintype "bidirectional"))
      (node (ref "U3") (pin "8") (pinfunction "GND_8") (pintype "bidirectional"))
      (node (ref "U4") (pin "3") (pinfunction "G_3") (pintype "bidirectional"))
      (node (ref "U5") (pin "2") (pinfunction "G_2") (pintype "bidirectional"))
      (node (ref "U6") (pin "2") (pinfunction "GND_2") (pintype "bidirectional"))
      (node (ref "USB1") (pin "P4") (pinfunction "USBID_P4") (pintype "bidirectional"))
      (node (ref "USB1") (pin "P5") (pinfunction "GND_P5") (pintype "bidirectional"))
      (node (ref "VREG1") (pin "2") (pinfunction "GND_2") (pintype "bidirectional"))
      (node (ref "X1") (pin "2") (pinfunction "GND_2") (pintype "bidirectional"))
    )
    (net (code "65") (name "PWR-VCC") (class "Default")
      (node (ref "C16") (pin "1") (pinfunction "P$1_1") (pintype "passive"))
      (node (ref "C18") (pin "1") (pinfunction "P$1_1") (pintype "passive"))
      (node (ref "C19") (pin "1") (pinfunction "P$1_1") (pintype "passive"))
      (node (ref "C2") (pin "1") (pinfunction "P$1_1") (pintype "passive"))
      (node (ref "C20") (pin "1") (pinfunction "P$1_1") (pintype "passive"))
      (node (ref "C21") (pin "1") (pinfunction "P$1_1") (pintype "passive"))
      (node (ref "C22") (pin "1") (pinfunction "P$1_1") (pintype "passive"))
      (node (ref "C26") (pin "1") (pinfunction "P$1_1") (pintype "passive"))
      (node (ref "C27") (pin "1") (pinfunction "P$1_1") (pintype "passive"))
      (node (ref "C28") (pin "1") (pinfunction "P$1_1") (pintype "passive"))
      (node (ref "C3") (pin "1") (pinfunction "P$1_1") (pintype "passive"))
      (node (ref "C30") (pin "1") (pinfunction "P$1_1") (pintype "passive"))
      (node (ref "C32") (pin "1") (pinfunction "P$1_1") (pintype "passive"))
      (node (ref "C34") (pin "1") (pinfunction "P$1_1") (pintype "passive"))
      (node (ref "C35") (pin "1") (pinfunction "P$1_1") (pintype "passive"))
      (node (ref "C36") (pin "1") (pinfunction "P$1_1") (pintype "passive"))
      (node (ref "C37") (pin "1") (pinfunction "P$1_1") (pintype "passive"))
      (node (ref "C7") (pin "1") (pinfunction "P$1_1") (pintype "passive"))
      (node (ref "C9") (pin "2") (pinfunction "P$2_2") (pintype "passive"))
      (node (ref "CN2") (pin "4") (pinfunction "VCC_4") (pintype "bidirectional"))
      (node (ref "CN2") (pin "SW1") (pinfunction "SW1_SW1") (pintype "bidirectional"))
      (node (ref "CN6") (pin "1") (pinfunction "P$1_1") (pintype "passive"))
      (node (ref "D1") (pin "C") (pinfunction "C_C") (pintype "passive"))
      (node (ref "FAN1") (pin "3") (pinfunction "3_3") (pintype "bidirectional"))
      (node (ref "FAN2") (pin "3") (pinfunction "3_3") (pintype "bidirectional"))
      (node (ref "FAN3") (pin "3") (pinfunction "3_3") (pintype "bidirectional"))
      (node (ref "FAN4") (pin "3") (pinfunction "3_3") (pintype "bidirectional"))
      (node (ref "J4") (pin "1") (pinfunction "1_1") (pintype "bidirectional"))
      (node (ref "L1") (pin "1") (pinfunction "P$1_1") (pintype "passive"))
      (node (ref "NY1") (pin "P1") (pinfunction "P1_P1") (pintype "input"))
      (node (ref "R5") (pin "2") (pinfunction "P$2_2") (pintype "passive"))
      (node (ref "SW1") (pin "3") (pinfunction "P$2_3") (pintype "passive"))
      (node (ref "SW3") (pin "1") (pinfunction "P$1_1") (pintype "passive"))
      (node (ref "SW3") (pin "3") (pinfunction "P$1_3") (pintype "passive"))
      (node (ref "U1") (pin "1") (pinfunction "VBAT_1") (pintype "bidirectional"))
      (node (ref "U1") (pin "19") (pinfunction "VCC_19") (pintype "bidirectional"))
      (node (ref "U1") (pin "32") (pinfunction "VCC_32") (pintype "bidirectional"))
      (node (ref "U1") (pin "48") (pinfunction "VCC_48") (pintype "bidirectional"))
      (node (ref "U1") (pin "64") (pinfunction "VCC_64") (pintype "bidirectional"))
      (node (ref "U6") (pin "5") (pinfunction "VOUT_5") (pintype "bidirectional"))
      (node (ref "VREG1") (pin "3") (pinfunction "VO_3") (pintype "bidirectional"))
      (node (ref "X1") (pin "4") (pinfunction "VCC_4") (pintype "bidirectional"))
    )
    (net (code "66") (name "PWR-VCCA") (class "Default")
      (node (ref "C23") (pin "1") (pinfunction "P$1_1") (pintype "passive"))
      (node (ref "C24") (pin "1") (pinfunction "P$1_1") (pintype "passive"))
      (node (ref "C25") (pin "1") (pinfunction "P$1_1") (pintype "passive"))
      (node (ref "C31") (pin "1") (pinfunction "P$1_1") (pintype "passive"))
      (node (ref "C33") (pin "1") (pinfunction "P$1_1") (pintype "passive"))
      (node (ref "C39") (pin "1") (pinfunction "P$1_1") (pintype "passive"))
      (node (ref "C4") (pin "1") (pinfunction "P$1_1") (pintype "passive"))
      (node (ref "C41") (pin "1") (pinfunction "P$1_1") (pintype "passive"))
      (node (ref "C42") (pin "1") (pinfunction "P$1_1") (pintype "passive"))
      (node (ref "J1") (pin "6") (pinfunction "P$6_6") (pintype "passive"))
      (node (ref "L1") (pin "2") (pinfunction "P$2_2") (pintype "passive"))
      (node (ref "U1") (pin "13") (pinfunction "VCCA_13") (pintype "bidirectional"))
      (node (ref "U2") (pin "6") (pinfunction "VCC_6") (pintype "bidirectional"))
      (node (ref "U4") (pin "1") (pinfunction "V_1") (pintype "bidirectional"))
      (node (ref "U5") (pin "5") (pinfunction "V_5") (pintype "bidirectional"))
    )
    (net (code "67") (name "PWR-VCCM") (class "Default")
      (node (ref "C1") (pin "1") (pinfunction "P$1_1") (pintype "passive"))
      (node (ref "C44") (pin "1") (pinfunction "P$1_1") (pintype "passive"))
      (node (ref "FAN1") (pin "1") (pinfunction "1_1") (pintype "bidirectional"))
      (node (ref "FAN2") (pin "1") (pinfunction "1_1") (pintype "bidirectional"))
      (node (ref "FAN3") (pin "1") (pinfunction "1_1") (pintype "bidirectional"))
      (node (ref "FAN4") (pin "1") (pinfunction "1_1") (pintype "bidirectional"))
      (node (ref "J1") (pin "2") (pinfunction "P$2_2") (pintype "passive"))
      (node (ref "J1") (pin "4") (pinfunction "P$4_4") (pintype "passive"))
      (node (ref "R14") (pin "1") (pinfunction "P$1_1") (pintype "passive"))
      (node (ref "U2") (pin "4") (pinfunction "IN-_4") (pintype "bidirectional"))
      (node (ref "VREG1") (pin "1") (pinfunction "VI_1") (pintype "bidirectional"))
    )
    (net (code "68") (name "unconnected-(CN2-DAT1-Pad8)") (class "Default")
      (node (ref "CN2") (pin "8") (pinfunction "DAT1_8") (pintype "bidirectional"))
    )
    (net (code "69") (name "unconnected-(CN2-DAT2-Pad1)") (class "Default")
      (node (ref "CN2") (pin "1") (pinfunction "DAT2_1") (pintype "bidirectional"))
    )
    (net (code "70") (name "unconnected-(U1-OSCOUT-Pad6)") (class "Default")
      (node (ref "U1") (pin "6") (pinfunction "OSCOUT_6") (pintype "bidirectional"))
    )
    (net (code "71") (name "unconnected-(U1-PA10-Pad43)") (class "Default")
      (node (ref "U1") (pin "43") (pinfunction "PA10_43") (pintype "bidirectional"))
    )
    (net (code "72") (name "unconnected-(U1-PA14-Pad49)") (class "Default")
      (node (ref "U1") (pin "49") (pinfunction "PA14_49") (pintype "bidirectional"))
    )
    (net (code "73") (name "unconnected-(U1-PB7-Pad59)") (class "Default")
      (node (ref "U1") (pin "59") (pinfunction "PB7_59") (pintype "bidirectional"))
    )
    (net (code "74") (name "unconnected-(U1-PB10-Pad29)") (class "Default")
      (node (ref "U1") (pin "29") (pinfunction "PB10_29") (pintype "bidirectional"))
    )
    (net (code "75") (name "unconnected-(U1-PB11-Pad30)") (class "Default")
      (node (ref "U1") (pin "30") (pinfunction "PB11_30") (pintype "bidirectional"))
    )
    (net (code "76") (name "unconnected-(U1-PC3-Pad11)") (class "Default")
      (node (ref "U1") (pin "11") (pinfunction "PC3_11") (pintype "bidirectional"))
    )
    (net (code "77") (name "unconnected-(U1-PC4-Pad24)") (class "Default")
      (node (ref "U1") (pin "24") (pinfunction "PC4_24") (pintype "bidirectional"))
    )
    (net (code "78") (name "unconnected-(U1-PC12-Pad53)") (class "Default")
      (node (ref "U1") (pin "53") (pinfunction "PC12_53") (pintype "bidirectional"))
    )
    (net (code "79") (name "unconnected-(U1-PC13-Pad2)") (class "Default")
      (node (ref "U1") (pin "2") (pinfunction "PC13_2") (pintype "bidirectional"))
    )
    (net (code "80") (name "unconnected-(U1-PC14-Pad3)") (class "Default")
      (node (ref "U1") (pin "3") (pinfunction "PC14_3") (pintype "bidirectional"))
    )
    (net (code "81") (name "unconnected-(U1-PC15-Pad4)") (class "Default")
      (node (ref "U1") (pin "4") (pinfunction "PC15_4") (pintype "bidirectional"))
    )
    (net (code "82") (name "unconnected-(U3-COM-Pad9)") (class "Default")
      (node (ref "U3") (pin "9") (pinfunction "COM_9") (pintype "bidirectional"))
    )
    (net (code "83") (name "unconnected-(U3-IN4-Pad4)") (class "Default")
      (node (ref "U3") (pin "4") (pinfunction "IN4_4") (pintype "input"))
    )
    (net (code "84") (name "unconnected-(U3-IN5-Pad5)") (class "Default")
      (node (ref "U3") (pin "5") (pinfunction "IN5_5") (pintype "input"))
    )
    (net (code "85") (name "unconnected-(U3-IN6-Pad6)") (class "Default")
      (node (ref "U3") (pin "6") (pinfunction "IN6_6") (pintype "input"))
    )
    (net (code "86") (name "unconnected-(U3-IN7-Pad7)") (class "Default")
      (node (ref "U3") (pin "7") (pinfunction "IN7_7") (pintype "input"))
    )
    (net (code "87") (name "unconnected-(U3-OUT4-Pad13)") (class "Default")
      (node (ref "U3") (pin "13") (pinfunction "OUT4_13") (pintype "output"))
    )
    (net (code "88") (name "unconnected-(U3-OUT5-Pad12)") (class "Default")
      (node (ref "U3") (pin "12") (pinfunction "OUT5_12") (pintype "output"))
    )
    (net (code "89") (name "unconnected-(U3-OUT6-Pad11)") (class "Default")
      (node (ref "U3") (pin "11") (pinfunction "OUT6_11") (pintype "output"))
    )
    (net (code "90") (name "unconnected-(U3-OUT7-Pad10)") (class "Default")
      (node (ref "U3") (pin "10") (pinfunction "OUT7_10") (pintype "output"))
    )
    (net (code "91") (name "unconnected-(U6-PWRGD-Pad4)") (class "Default")
      (node (ref "U6") (pin "4") (pinfunction "PWRGD_4") (pintype "bidirectional"))
    )
  )
)
